# crz7shlda0.net
KiCad netlist of a schematic drawn in EAGLE
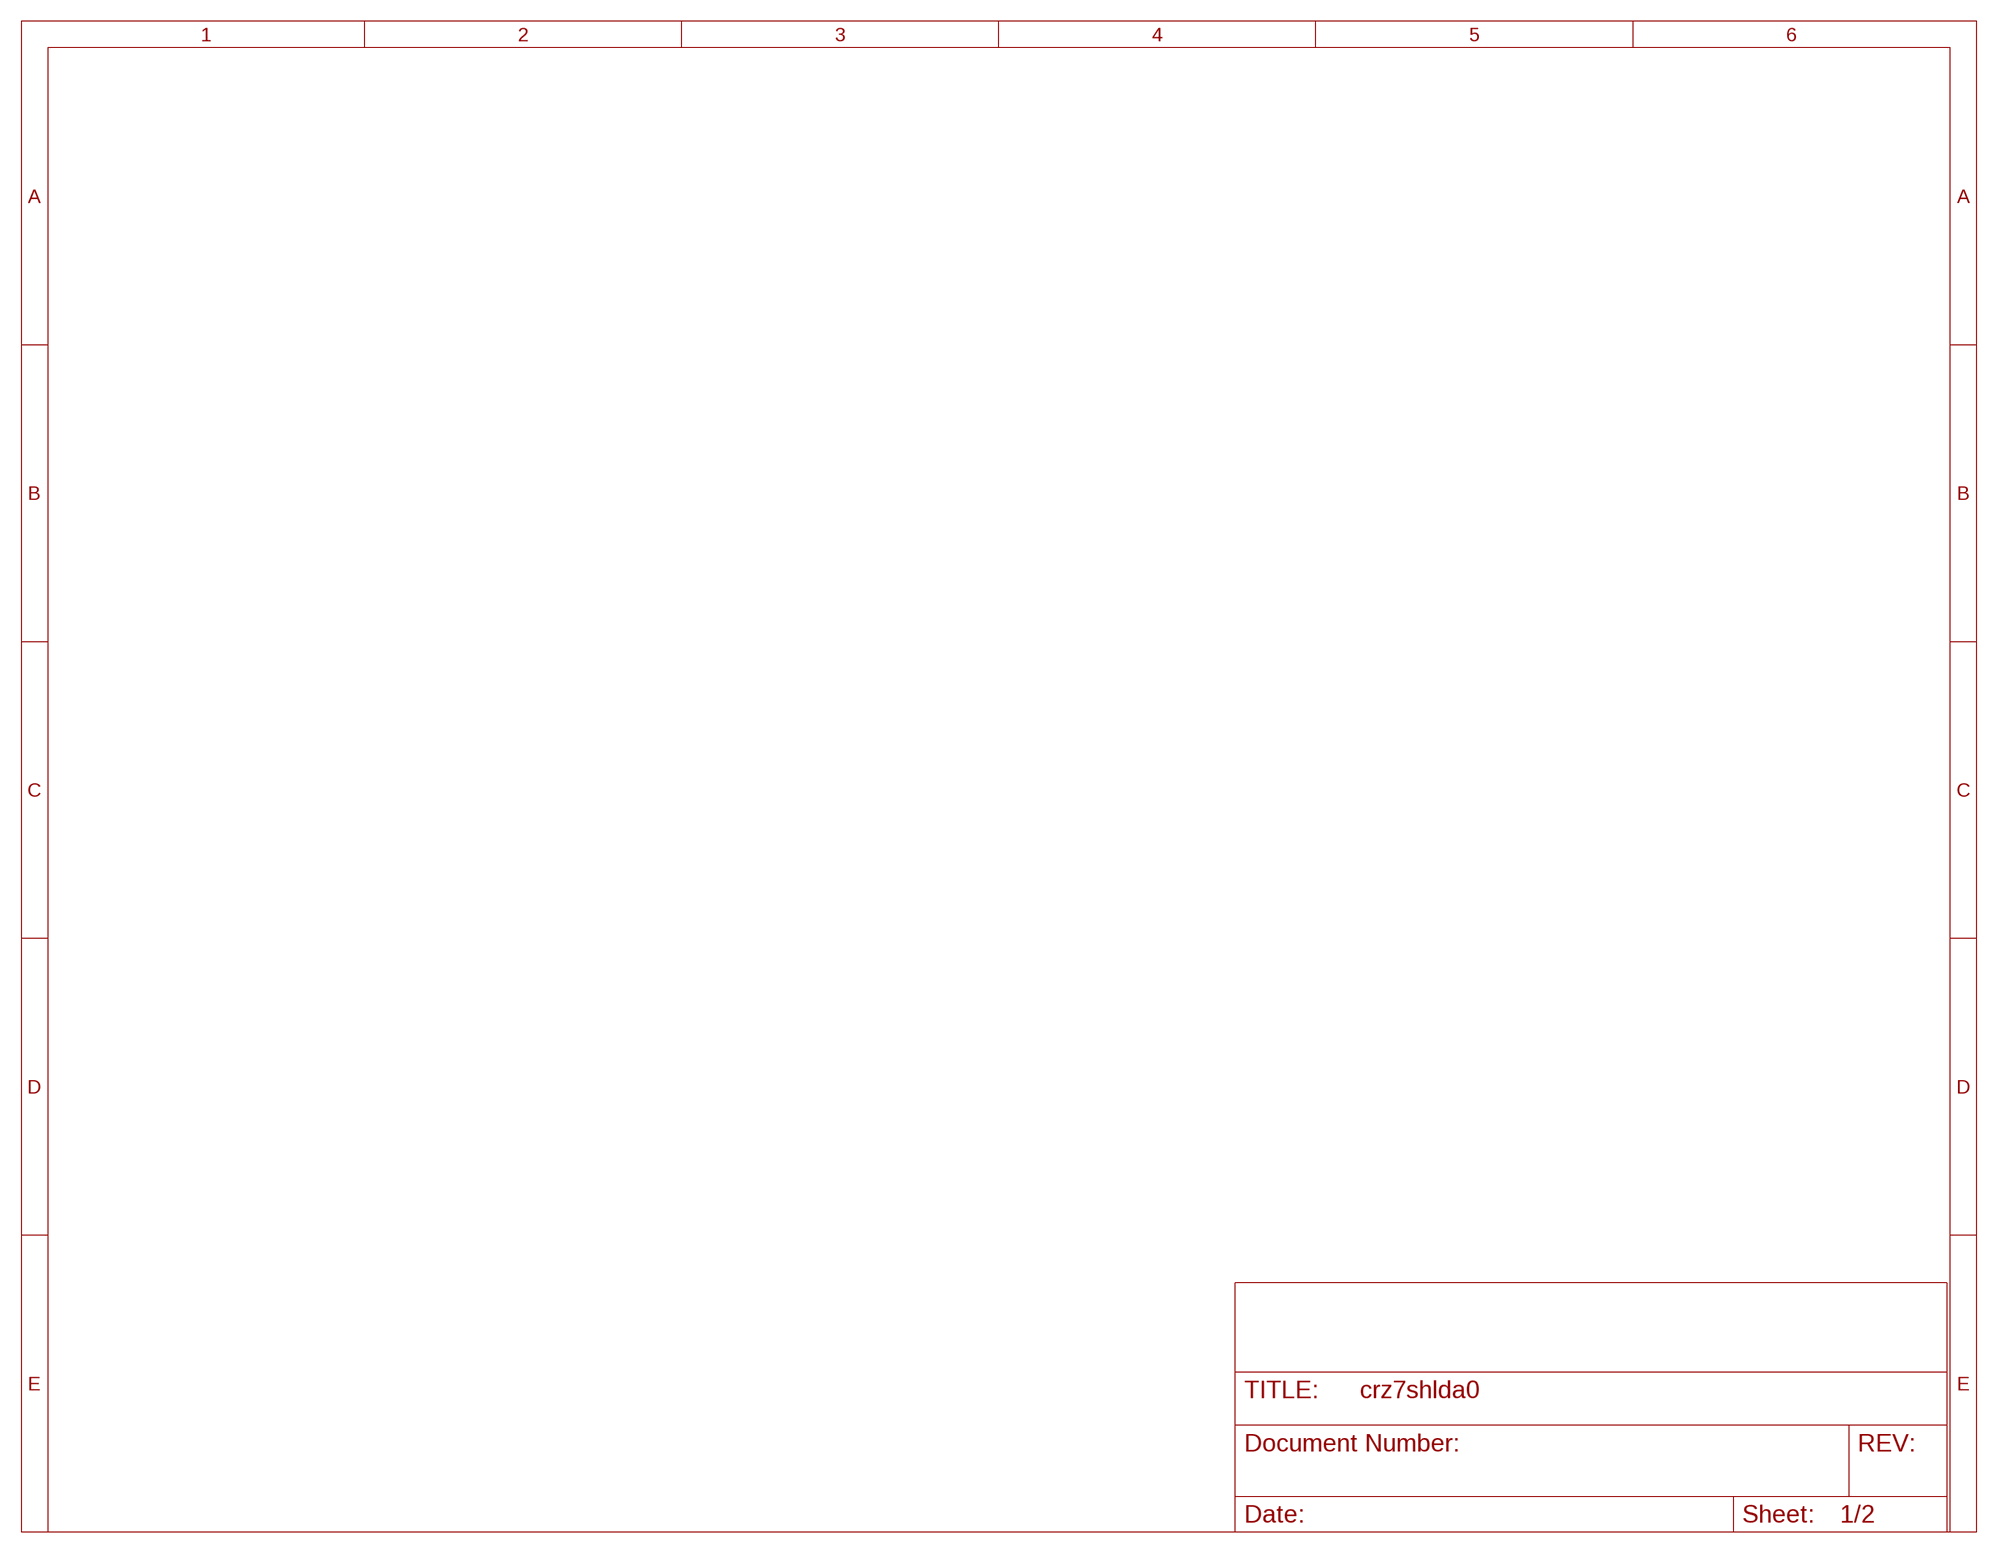
[diagram p0: schematic, sheet 1]
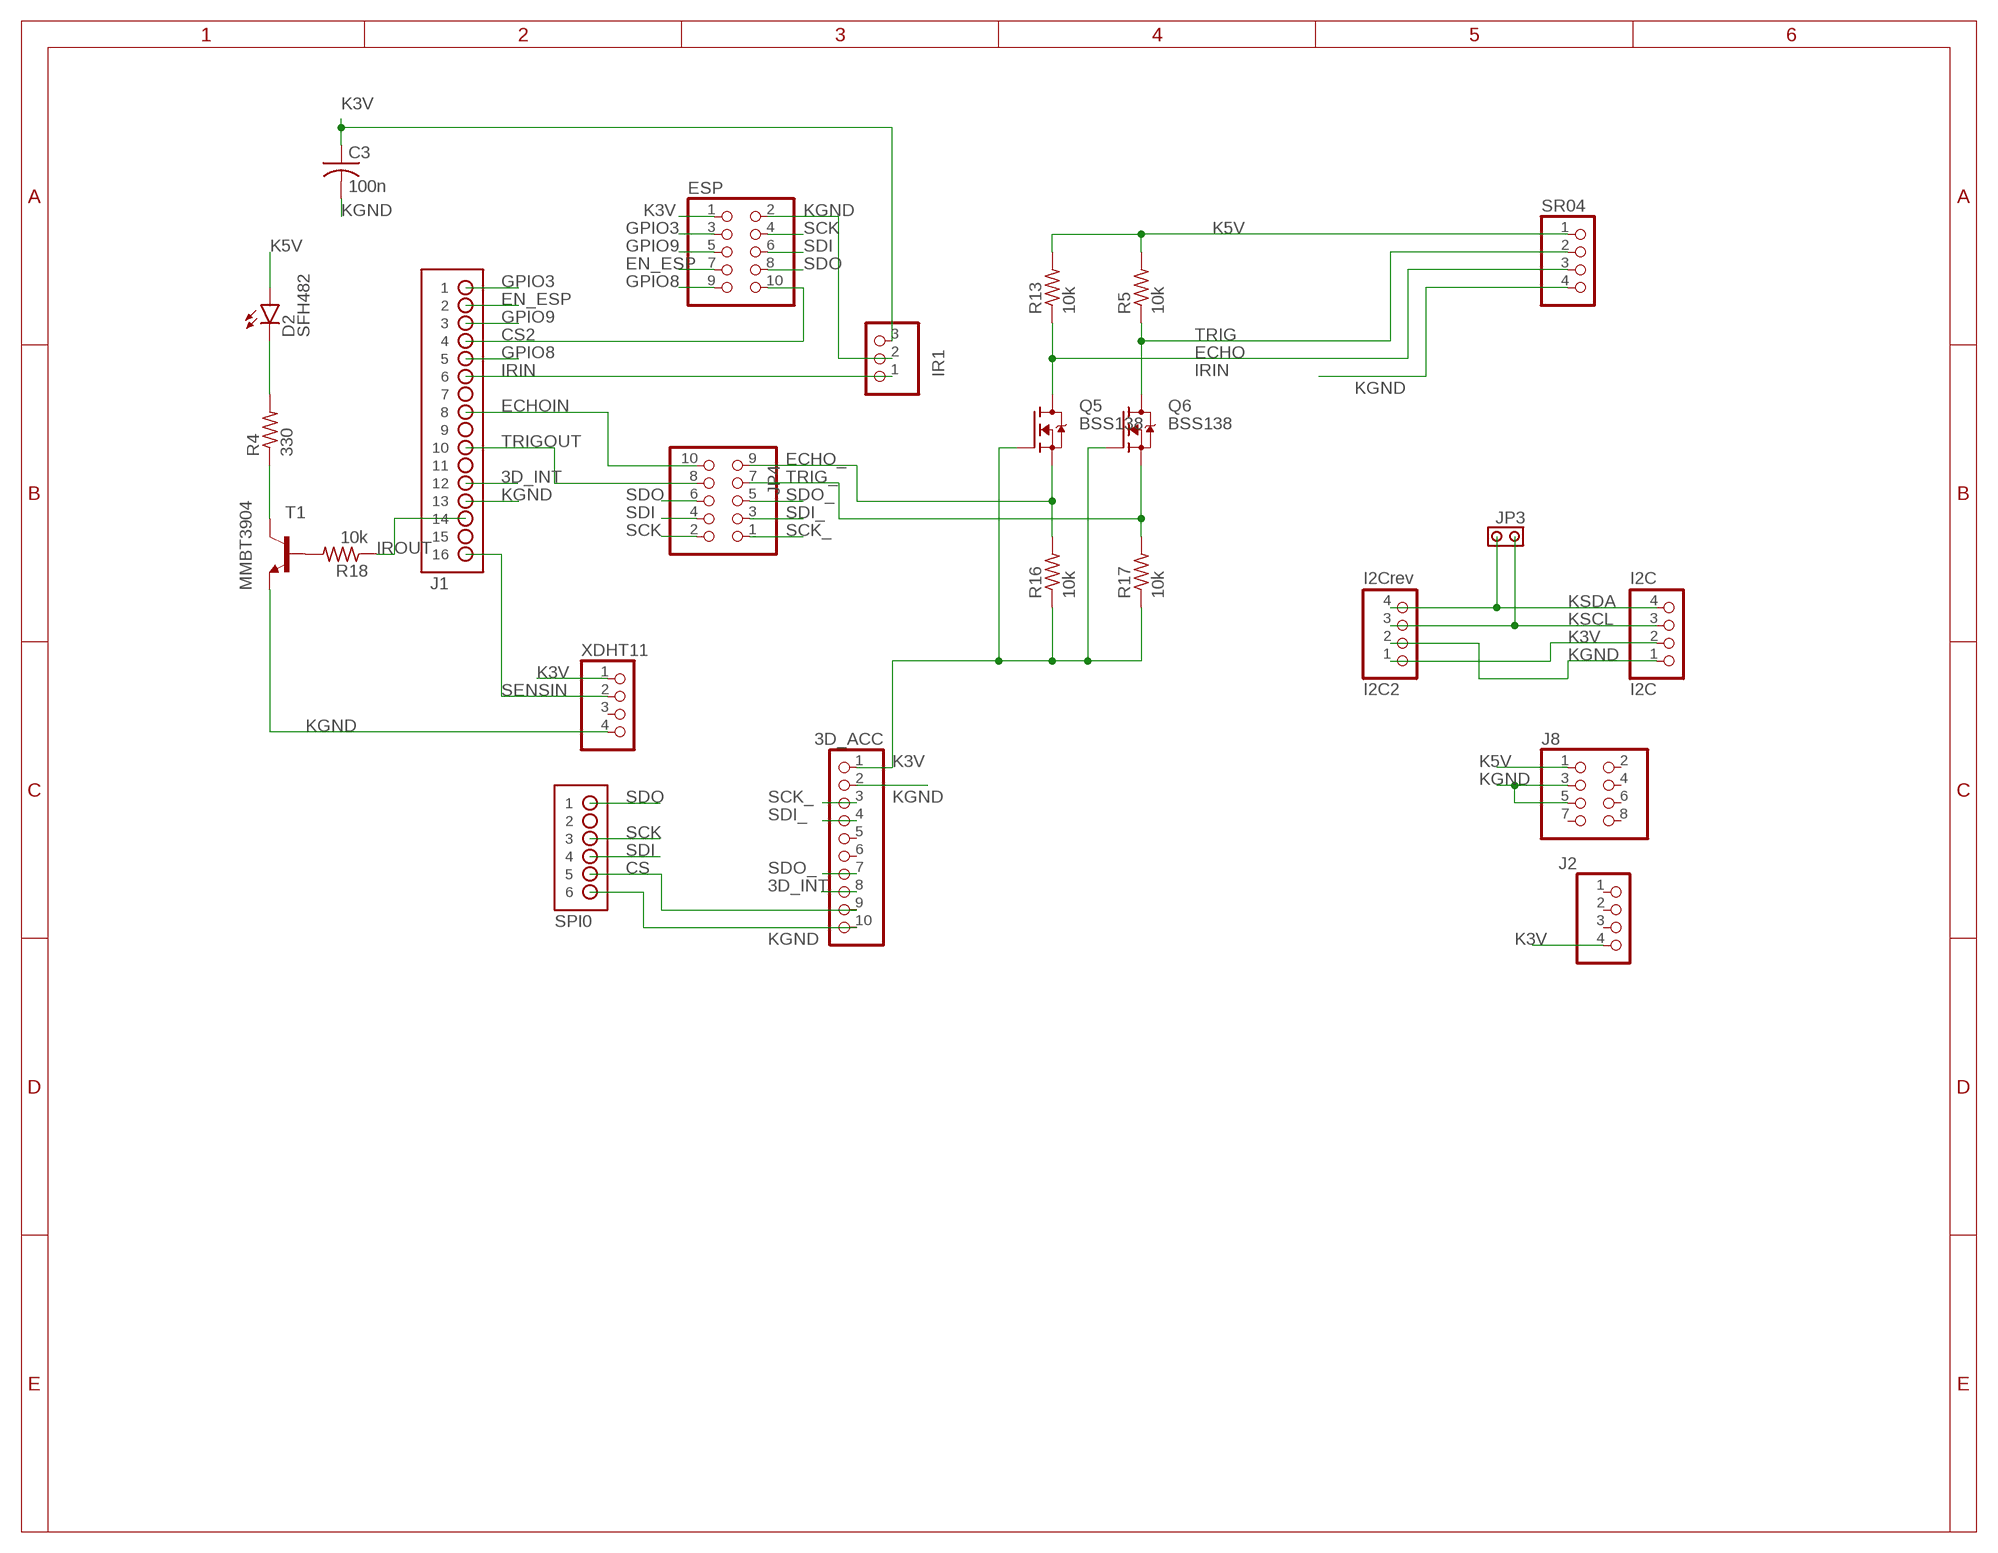
[diagram p1: schematic, sheet 2]

(export (version "E")
  (design (tool "Eeschema 10.0.6"))
  (components
    (comp (ref "3D_ACC")
      (value "PINHD-1X10")
      (footprint "eagle-import:1X10")
      (libsource (lib "eagle-import") (part "PINHD-1X10"))
    )
    (comp (ref "C3")
      (value "100n")
      (footprint "eagle-import:C0402")
      (libsource (lib "eagle-import") (part "C-USC0402"))
    )
    (comp (ref "D2")
      (value "SFH482")
      (footprint "eagle-import:SFH482")
      (libsource (lib "eagle-import") (part "SFH482"))
    )
    (comp (ref "ESP")
      (value "PINHD-2X5")
      (footprint "eagle-import:2X05")
      (libsource (lib "eagle-import") (part "PINHD-2X5"))
    )
    (comp (ref "I2C")
      (value "I2C")
      (footprint "eagle-import:1X04")
      (libsource (lib "eagle-import") (part "PINHD-1X4"))
    )
    (comp (ref "I2C2")
      (value "I2Crev")
      (footprint "eagle-import:1X04")
      (libsource (lib "eagle-import") (part "PINHD-1X4"))
    )
    (comp (ref "IR1")
      (value "PINHD-1X3")
      (footprint "eagle-import:1X03")
      (libsource (lib "eagle-import") (part "PINHD-1X3"))
    )
    (comp (ref "J1")
      (value "HDR-2X8")
      (footprint "eagle-import:HDR-2X8")
      (libsource (lib "eagle-import") (part "HDR-2X8"))
    )
    (comp (ref "J2")
      (value "PINHD-1X4")
      (footprint "eagle-import:1X04")
      (libsource (lib "eagle-import") (part "PINHD-1X4"))
    )
    (comp (ref "J8")
      (value "PINHD-2X4")
      (footprint "eagle-import:2X04")
      (libsource (lib "eagle-import") (part "PINHD-2X4"))
    )
    (comp (ref "JP3")
      (value "JPR-1X2")
      (footprint "eagle-import:JPR-1X2")
      (libsource (lib "eagle-import") (part "JPR-1X2"))
    )
    (comp (ref "JP4")
      (value "PINHD-2X5")
      (footprint "eagle-import:2X05")
      (libsource (lib "eagle-import") (part "PINHD-2X5"))
    )
    (comp (ref "Q5")
      (value "BSS138")
      (footprint "eagle-import:SOT23")
      (fields (field (name "MF") "Fairchild"))
      (libsource (lib "eagle-import") (part "BSS138"))
    )
    (comp (ref "Q6")
      (value "BSS138")
      (footprint "eagle-import:SOT23")
      (fields (field (name "MF") "Fairchild"))
      (libsource (lib "eagle-import") (part "BSS138"))
    )
    (comp (ref "R4")
      (value "330")
      (footprint "eagle-import:R0402")
      (libsource (lib "eagle-import") (part "R-US_R0402"))
    )
    (comp (ref "R5")
      (value "10k")
      (footprint "eagle-import:R0402")
      (libsource (lib "eagle-import") (part "R-US_R0402"))
    )
    (comp (ref "R13")
      (value "10k")
      (footprint "eagle-import:R0402")
      (libsource (lib "eagle-import") (part "R-US_R0402"))
    )
    (comp (ref "R16")
      (value "10k")
      (footprint "eagle-import:R0402")
      (libsource (lib "eagle-import") (part "R-US_R0402"))
    )
    (comp (ref "R17")
      (value "10k")
      (footprint "eagle-import:R0402")
      (libsource (lib "eagle-import") (part "R-US_R0402"))
    )
    (comp (ref "R18")
      (value "10k")
      (footprint "eagle-import:R0402")
      (libsource (lib "eagle-import") (part "R-US_R0402"))
    )
    (comp (ref "SPI0")
      (value "HDR-2X3")
      (footprint "eagle-import:HDR-2X3")
      (libsource (lib "eagle-import") (part "HDR-2X3"))
    )
    (comp (ref "SR04")
      (value "PINHD-1X4")
      (footprint "eagle-import:1X04")
      (libsource (lib "eagle-import") (part "PINHD-1X4"))
    )
    (comp (ref "T1")
      (value "MMBT3904")
      (footprint "eagle-import:SOT23-BEC")
      (libsource (lib "eagle-import") (part "-NPN-SOT23-BECMMBT3904LT1"))
    )
    (comp (ref "XDHT11")
      (value "PINHD-1X4")
      (footprint "eagle-import:1X04")
      (libsource (lib "eagle-import") (part "PINHD-1X4"))
    )
  )
  (nets
    (net (code "1") (name "3D_INT") (class "Default")
      (node (ref "3D_ACC") (pin "8") (pinfunction "8_8") (pintype "passive"))
      (node (ref "J1") (pin "12") (pinfunction "12_12") (pintype "passive"))
    )
    (net (code "2") (name "CS") (class "Default")
      (node (ref "3D_ACC") (pin "9") (pinfunction "9_9") (pintype "passive"))
      (node (ref "SPI0") (pin "5") (pinfunction "5_5") (pintype "passive"))
    )
    (net (code "3") (name "CS2") (class "Default")
      (node (ref "ESP") (pin "10") (pinfunction "10_10") (pintype "passive"))
      (node (ref "J1") (pin "4") (pinfunction "4_4") (pintype "passive"))
    )
    (net (code "4") (name "ECHO") (class "Default")
      (node (ref "Q5") (pin "3") (pinfunction "D_3") (pintype "passive"))
      (node (ref "R13") (pin "1") (pinfunction "1_1") (pintype "passive"))
      (node (ref "SR04") (pin "3") (pinfunction "3_3") (pintype "passive"))
    )
    (net (code "5") (name "ECHOIN") (class "Default")
      (node (ref "J1") (pin "8") (pinfunction "8_8") (pintype "passive"))
      (node (ref "JP4") (pin "10") (pinfunction "10_10") (pintype "passive"))
    )
    (net (code "6") (name "ECHO_") (class "Default")
      (node (ref "JP4") (pin "9") (pinfunction "9_9") (pintype "passive"))
      (node (ref "Q5") (pin "2") (pinfunction "S_2") (pintype "passive"))
      (node (ref "R16") (pin "2") (pinfunction "2_2") (pintype "passive"))
    )
    (net (code "7") (name "EN_ESP") (class "Default")
      (node (ref "ESP") (pin "7") (pinfunction "7_7") (pintype "passive"))
      (node (ref "J1") (pin "2") (pinfunction "2_2") (pintype "passive"))
    )
    (net (code "8") (name "GPIO3") (class "Default")
      (node (ref "ESP") (pin "3") (pinfunction "3_3") (pintype "passive"))
      (node (ref "J1") (pin "1") (pinfunction "1_1") (pintype "passive"))
    )
    (net (code "9") (name "GPIO8") (class "Default")
      (node (ref "ESP") (pin "9") (pinfunction "9_9") (pintype "passive"))
      (node (ref "J1") (pin "5") (pinfunction "5_5") (pintype "passive"))
    )
    (net (code "10") (name "GPIO9") (class "Default")
      (node (ref "ESP") (pin "5") (pinfunction "5_5") (pintype "passive"))
      (node (ref "J1") (pin "3") (pinfunction "3_3") (pintype "passive"))
    )
    (net (code "11") (name "IRIN") (class "Default")
      (node (ref "IR1") (pin "1") (pinfunction "1_1") (pintype "passive"))
      (node (ref "J1") (pin "6") (pinfunction "6_6") (pintype "passive"))
    )
    (net (code "12") (name "IROUT") (class "Default")
      (node (ref "J1") (pin "14") (pinfunction "14_14") (pintype "passive"))
      (node (ref "R18") (pin "1") (pinfunction "1_1") (pintype "passive"))
    )
    (net (code "13") (name "K3V") (class "Default")
      (node (ref "3D_ACC") (pin "1") (pinfunction "1_1") (pintype "passive"))
      (node (ref "C3") (pin "1") (pinfunction "1_1") (pintype "passive"))
      (node (ref "ESP") (pin "1") (pinfunction "1_1") (pintype "passive"))
      (node (ref "I2C") (pin "2") (pinfunction "2_2") (pintype "passive"))
      (node (ref "I2C2") (pin "1") (pinfunction "1_1") (pintype "passive"))
      (node (ref "IR1") (pin "3") (pinfunction "3_3") (pintype "passive"))
      (node (ref "J2") (pin "4") (pinfunction "4_4") (pintype "passive"))
      (node (ref "Q5") (pin "1") (pinfunction "G_1") (pintype "passive"))
      (node (ref "Q6") (pin "1") (pinfunction "G_1") (pintype "passive"))
      (node (ref "R16") (pin "1") (pinfunction "1_1") (pintype "passive"))
      (node (ref "R17") (pin "1") (pinfunction "1_1") (pintype "passive"))
      (node (ref "XDHT11") (pin "1") (pinfunction "1_1") (pintype "passive"))
    )
    (net (code "14") (name "K5V") (class "Default")
      (node (ref "D2") (pin "A") (pinfunction "A_A") (pintype "passive"))
      (node (ref "J8") (pin "1") (pinfunction "1_1") (pintype "passive"))
      (node (ref "R13") (pin "2") (pinfunction "2_2") (pintype "passive"))
      (node (ref "R5") (pin "2") (pinfunction "2_2") (pintype "passive"))
      (node (ref "SR04") (pin "1") (pinfunction "1_1") (pintype "passive"))
    )
    (net (code "15") (name "KGND") (class "Default")
      (node (ref "3D_ACC") (pin "10") (pinfunction "10_10") (pintype "passive"))
      (node (ref "3D_ACC") (pin "2") (pinfunction "2_2") (pintype "passive"))
      (node (ref "C3") (pin "2") (pinfunction "2_2") (pintype "passive"))
      (node (ref "ESP") (pin "2") (pinfunction "2_2") (pintype "passive"))
      (node (ref "I2C") (pin "1") (pinfunction "1_1") (pintype "passive"))
      (node (ref "I2C2") (pin "2") (pinfunction "2_2") (pintype "passive"))
      (node (ref "IR1") (pin "2") (pinfunction "2_2") (pintype "passive"))
      (node (ref "J1") (pin "13") (pinfunction "13_13") (pintype "passive"))
      (node (ref "J8") (pin "3") (pinfunction "3_3") (pintype "passive"))
      (node (ref "J8") (pin "5") (pinfunction "5_5") (pintype "passive"))
      (node (ref "SPI0") (pin "6") (pinfunction "6_6") (pintype "passive"))
      (node (ref "SR04") (pin "4") (pinfunction "4_4") (pintype "passive"))
      (node (ref "T1") (pin "E") (pinfunction "E_E") (pintype "passive"))
      (node (ref "XDHT11") (pin "4") (pinfunction "4_4") (pintype "passive"))
    )
    (net (code "16") (name "KSCL") (class "Default")
      (node (ref "I2C") (pin "3") (pinfunction "3_3") (pintype "passive"))
      (node (ref "I2C2") (pin "3") (pinfunction "3_3") (pintype "passive"))
      (node (ref "JP3") (pin "2") (pinfunction "2_2") (pintype "passive"))
    )
    (net (code "17") (name "KSDA") (class "Default")
      (node (ref "I2C") (pin "4") (pinfunction "4_4") (pintype "passive"))
      (node (ref "I2C2") (pin "4") (pinfunction "4_4") (pintype "passive"))
      (node (ref "JP3") (pin "1") (pinfunction "1_1") (pintype "passive"))
    )
    (net (code "18") (name "Net-(D2-C)") (class "Default")
      (node (ref "D2") (pin "K") (pinfunction "C_K") (pintype "passive"))
      (node (ref "R4") (pin "2") (pinfunction "2_2") (pintype "passive"))
    )
    (net (code "19") (name "Net-(R4-Pad1)") (class "Default")
      (node (ref "R4") (pin "1") (pinfunction "1_1") (pintype "passive"))
      (node (ref "T1") (pin "C") (pinfunction "C_C") (pintype "passive"))
    )
    (net (code "20") (name "Net-(R18-Pad2)") (class "Default")
      (node (ref "R18") (pin "2") (pinfunction "2_2") (pintype "passive"))
      (node (ref "T1") (pin "B") (pinfunction "B_B") (pintype "passive"))
    )
    (net (code "21") (name "SCK") (class "Default")
      (node (ref "ESP") (pin "4") (pinfunction "4_4") (pintype "passive"))
      (node (ref "JP4") (pin "2") (pinfunction "2_2") (pintype "passive"))
      (node (ref "SPI0") (pin "3") (pinfunction "3_3") (pintype "passive"))
    )
    (net (code "22") (name "SCK_") (class "Default")
      (node (ref "3D_ACC") (pin "3") (pinfunction "3_3") (pintype "passive"))
      (node (ref "JP4") (pin "1") (pinfunction "1_1") (pintype "passive"))
    )
    (net (code "23") (name "SDI") (class "Default")
      (node (ref "ESP") (pin "6") (pinfunction "6_6") (pintype "passive"))
      (node (ref "JP4") (pin "4") (pinfunction "4_4") (pintype "passive"))
      (node (ref "SPI0") (pin "4") (pinfunction "4_4") (pintype "passive"))
    )
    (net (code "24") (name "SDI_") (class "Default")
      (node (ref "3D_ACC") (pin "4") (pinfunction "4_4") (pintype "passive"))
      (node (ref "JP4") (pin "3") (pinfunction "3_3") (pintype "passive"))
    )
    (net (code "25") (name "SDO") (class "Default")
      (node (ref "ESP") (pin "8") (pinfunction "8_8") (pintype "passive"))
      (node (ref "JP4") (pin "6") (pinfunction "6_6") (pintype "passive"))
      (node (ref "SPI0") (pin "1") (pinfunction "1_1") (pintype "passive"))
    )
    (net (code "26") (name "SDO_") (class "Default")
      (node (ref "3D_ACC") (pin "7") (pinfunction "7_7") (pintype "passive"))
      (node (ref "JP4") (pin "5") (pinfunction "5_5") (pintype "passive"))
    )
    (net (code "27") (name "SENSIN") (class "Default")
      (node (ref "J1") (pin "16") (pinfunction "16_16") (pintype "passive"))
      (node (ref "XDHT11") (pin "2") (pinfunction "2_2") (pintype "passive"))
    )
    (net (code "28") (name "TRIG") (class "Default")
      (node (ref "Q6") (pin "3") (pinfunction "D_3") (pintype "passive"))
      (node (ref "R5") (pin "1") (pinfunction "1_1") (pintype "passive"))
      (node (ref "SR04") (pin "2") (pinfunction "2_2") (pintype "passive"))
    )
    (net (code "29") (name "TRIGOUT") (class "Default")
      (node (ref "J1") (pin "10") (pinfunction "10_10") (pintype "passive"))
      (node (ref "JP4") (pin "8") (pinfunction "8_8") (pintype "passive"))
    )
    (net (code "30") (name "TRIG_") (class "Default")
      (node (ref "JP4") (pin "7") (pinfunction "7_7") (pintype "passive"))
      (node (ref "Q6") (pin "2") (pinfunction "S_2") (pintype "passive"))
      (node (ref "R17") (pin "2") (pinfunction "2_2") (pintype "passive"))
    )
    (net (code "31") (name "unconnected-(3D_ACC-Pad5)") (class "Default")
      (node (ref "3D_ACC") (pin "5") (pinfunction "5_5") (pintype "passive"))
    )
    (net (code "32") (name "unconnected-(3D_ACC-Pad6)") (class "Default")
      (node (ref "3D_ACC") (pin "6") (pinfunction "6_6") (pintype "passive"))
    )
    (net (code "33") (name "unconnected-(J1-Pad7)") (class "Default")
      (node (ref "J1") (pin "7") (pinfunction "7_7") (pintype "passive"))
    )
    (net (code "34") (name "unconnected-(J1-Pad9)") (class "Default")
      (node (ref "J1") (pin "9") (pinfunction "9_9") (pintype "passive"))
    )
    (net (code "35") (name "unconnected-(J1-Pad11)") (class "Default")
      (node (ref "J1") (pin "11") (pinfunction "11_11") (pintype "passive"))
    )
    (net (code "36") (name "unconnected-(J1-Pad15)") (class "Default")
      (node (ref "J1") (pin "15") (pinfunction "15_15") (pintype "passive"))
    )
    (net (code "37") (name "unconnected-(J2-Pad1)") (class "Default")
      (node (ref "J2") (pin "1") (pinfunction "1_1") (pintype "passive"))
    )
    (net (code "38") (name "unconnected-(J2-Pad2)") (class "Default")
      (node (ref "J2") (pin "2") (pinfunction "2_2") (pintype "passive"))
    )
    (net (code "39") (name "unconnected-(J2-Pad3)") (class "Default")
      (node (ref "J2") (pin "3") (pinfunction "3_3") (pintype "passive"))
    )
    (net (code "40") (name "unconnected-(J8-Pad2)") (class "Default")
      (node (ref "J8") (pin "2") (pinfunction "2_2") (pintype "passive"))
    )
    (net (code "41") (name "unconnected-(J8-Pad4)") (class "Default")
      (node (ref "J8") (pin "4") (pinfunction "4_4") (pintype "passive"))
    )
    (net (code "42") (name "unconnected-(J8-Pad6)") (class "Default")
      (node (ref "J8") (pin "6") (pinfunction "6_6") (pintype "passive"))
    )
    (net (code "43") (name "unconnected-(J8-Pad7)") (class "Default")
      (node (ref "J8") (pin "7") (pinfunction "7_7") (pintype "passive"))
    )
    (net (code "44") (name "unconnected-(J8-Pad8)") (class "Default")
      (node (ref "J8") (pin "8") (pinfunction "8_8") (pintype "passive"))
    )
    (net (code "45") (name "unconnected-(SPI0-Pad2)") (class "Default")
      (node (ref "SPI0") (pin "2") (pinfunction "2_2") (pintype "passive"))
    )
    (net (code "46") (name "unconnected-(XDHT11-Pad3)") (class "Default")
      (node (ref "XDHT11") (pin "3") (pinfunction "3_3") (pintype "passive"))
    )
  )
)
